# design.net
KiCad netlist of a schematic drawn in Altium Designer
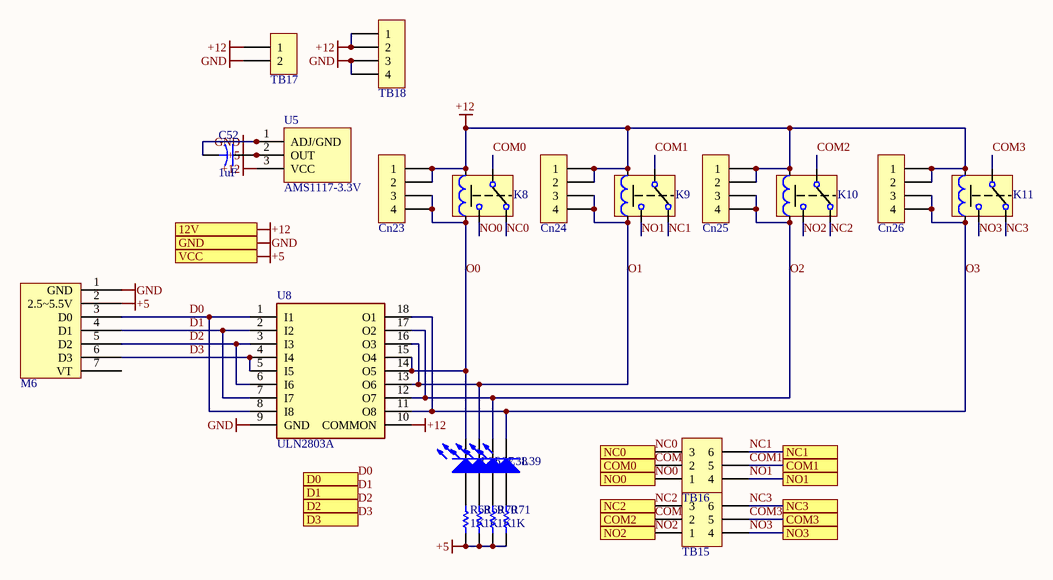
[diagram p0: 遙控繼電器.SchDoc]

(export (version "E")
  (design (tool "Eeschema 10.0.6"))
  (components
    (comp (ref "C52")
      (value "1uF")
      (footprint "CAP-1210")
      (description "電容")
      (libsource (lib "MyLibray") (part "Cap"))
    )
    (comp (ref "Cn23")
      (value "KF2510-4")
      (footprint "Connector_KF2510-4A")
      (description "接線端子")
      (libsource (lib "MyLibray") (part "Contact(4P)"))
    )
    (comp (ref "Cn24")
      (value "KF2510-4")
      (footprint "Connector_KF2510-4A")
      (description "接線端子")
      (libsource (lib "MyLibray") (part "Contact(4P)"))
    )
    (comp (ref "Cn25")
      (value "KF2510-4")
      (footprint "Connector_KF2510-4A")
      (description "接線端子")
      (libsource (lib "MyLibray") (part "Contact(4P)"))
    )
    (comp (ref "Cn26")
      (value "KF2510-4")
      (footprint "Connector_KF2510-4A")
      (description "接線端子")
      (libsource (lib "MyLibray") (part "Contact(4P)"))
    )
    (comp (ref "K8")
      (value "G2R-1-24VDC")
      (footprint "RELAY-HF41F-012-ZST")
      (description "繼電器")
      (libsource (lib "MyLibray") (part "Relay"))
    )
    (comp (ref "K9")
      (value "G2R-1-24VDC")
      (footprint "RELAY-HF41F-012-ZST")
      (description "繼電器")
      (libsource (lib "MyLibray") (part "Relay"))
    )
    (comp (ref "K10")
      (value "G2R-1-24VDC")
      (footprint "RELAY-HF41F-012-ZST")
      (description "繼電器")
      (libsource (lib "MyLibray") (part "Relay"))
    )
    (comp (ref "K11")
      (value "G2R-1-24VDC")
      (footprint "RELAY-HF41F-012-ZST")
      (description "繼電器")
      (libsource (lib "MyLibray") (part "Relay"))
    )
    (comp (ref "L36")
      (value "藍")
      (footprint "LED-1206")
      (description "LED")
      (libsource (lib "MyLibray") (part "LED"))
    )
    (comp (ref "L37")
      (value "藍")
      (footprint "LED-1206")
      (description "LED")
      (libsource (lib "MyLibray") (part "LED"))
    )
    (comp (ref "L38")
      (value "藍")
      (footprint "LED-1206")
      (description "LED")
      (libsource (lib "MyLibray") (part "LED"))
    )
    (comp (ref "L39")
      (value "藍")
      (footprint "LED-1206")
      (description "LED")
      (libsource (lib "MyLibray") (part "LED"))
    )
    (comp (ref "M6")
      (value "XR390")
      (footprint "XR390 Module")
      (description "遙控器模組")
      (libsource (lib "MyModule") (part "XR390"))
    )
    (comp (ref "R68")
      (value "1K")
      (footprint "Res-1206")
      (description "電阻")
      (libsource (lib "MyLibray") (part "Res"))
    )
    (comp (ref "R69")
      (value "1K")
      (footprint "Res-1206")
      (description "電阻")
      (libsource (lib "MyLibray") (part "Res"))
    )
    (comp (ref "R70")
      (value "1K")
      (footprint "Res-1206")
      (description "電阻")
      (libsource (lib "MyLibray") (part "Res"))
    )
    (comp (ref "R71")
      (value "1K")
      (footprint "Res-1206")
      (description "電阻")
      (libsource (lib "MyLibray") (part "Res"))
    )
    (comp (ref "TB15")
      (value "KF2EDGRT-5.08_6P")
      (footprint "Terminal block(KF2EDGRT-3.81_2*3P)")
      (description "端子台")
      (libsource (lib "MyLibray") (part "Terminal block(6P)"))
    )
    (comp (ref "TB16")
      (value "KF2EDGRT-5.08_6P")
      (footprint "Terminal block(KF2EDGRT-3.81_2*3P)")
      (description "端子台")
      (libsource (lib "MyLibray") (part "Terminal block(6P)"))
    )
    (comp (ref "TB17")
      (value "ZB25(2P)")
      (footprint "Terminal block(KF2EDGR-5.08 _2P)")
      (description "端子台")
      (libsource (lib "MyLibray") (part "Terminal block(2P)"))
    )
    (comp (ref "TB18")
      (value "KF2EDGRT-5.08_4P")
      (footprint "Terminal block(KF2EDGR-5.08 _4P)")
      (description "端子台")
      (libsource (lib "MyLibray") (part "Terminal block(4P)"))
    )
    (comp (ref "U5")
      (value "AMS1117-3.3V")
      (footprint "SOT 223")
      (description "降壓IC,LOD")
      (libsource (lib "MyLibray") (part "AMS1117"))
    )
    (comp (ref "U8")
      (value "ULN2803A")
      (footprint "DIP-18")
      (description "閘極驅動器 P型 50V 0.5A")
      (fields
        (field (name "MOUSER PART NUMBER") "757-TBD60183AFNGEL")
        (field (name "MANUFACTURER_PART_NUMBER") "TBD62083AFNG,EL")
      )
      (libsource (lib "MyLibray") (part "TBD62083A"))
    )
  )
  (nets
    (net (code "1") (name "+5") (class "Default")
      (node (ref "C52") (pin "1") (pinfunction "1_1") (pintype "passive"))
      (node (ref "M6") (pin "2") (pinfunction "2.5~5.5V_2") (pintype "passive"))
      (node (ref "R68") (pin "2") (pinfunction "2_2") (pintype "passive"))
      (node (ref "R69") (pin "2") (pinfunction "2_2") (pintype "passive"))
      (node (ref "R70") (pin "2") (pinfunction "2_2") (pintype "passive"))
      (node (ref "R71") (pin "2") (pinfunction "2_2") (pintype "passive"))
      (node (ref "U5") (pin "2") (pinfunction "OUT_2") (pintype "passive"))
    )
    (net (code "2") (name "+12") (class "Default")
      (node (ref "Cn23") (pin "1") (pinfunction "1_1") (pintype "passive"))
      (node (ref "Cn23") (pin "2") (pinfunction "2_2") (pintype "passive"))
      (node (ref "Cn24") (pin "1") (pinfunction "1_1") (pintype "passive"))
      (node (ref "Cn24") (pin "2") (pinfunction "2_2") (pintype "passive"))
      (node (ref "Cn25") (pin "1") (pinfunction "1_1") (pintype "passive"))
      (node (ref "Cn25") (pin "2") (pinfunction "2_2") (pintype "passive"))
      (node (ref "Cn26") (pin "1") (pinfunction "1_1") (pintype "passive"))
      (node (ref "Cn26") (pin "2") (pinfunction "2_2") (pintype "passive"))
      (node (ref "K10") (pin "4") (pinfunction "A1_4") (pintype "passive"))
      (node (ref "K11") (pin "4") (pinfunction "A1_4") (pintype "passive"))
      (node (ref "K8") (pin "4") (pinfunction "A1_4") (pintype "passive"))
      (node (ref "K9") (pin "4") (pinfunction "A1_4") (pintype "passive"))
      (node (ref "TB17") (pin "1") (pinfunction "1_1") (pintype "passive"))
      (node (ref "TB18") (pin "1") (pinfunction "1_1") (pintype "passive"))
      (node (ref "TB18") (pin "2") (pinfunction "2_2") (pintype "passive"))
      (node (ref "U5") (pin "3") (pinfunction "VCC_3") (pintype "power_in"))
      (node (ref "U8") (pin "10") (pinfunction "COMMON_10") (pintype "passive"))
    )
    (net (code "3") (name "/COM0") (class "Default")
      (node (ref "K8") (pin "1") (pinfunction "COM_1") (pintype "passive"))
      (node (ref "TB16") (pin "2") (pinfunction "2_2") (pintype "passive"))
    )
    (net (code "4") (name "/COM1") (class "Default")
      (node (ref "K9") (pin "1") (pinfunction "COM_1") (pintype "passive"))
      (node (ref "TB16") (pin "5") (pinfunction "5_5") (pintype "passive"))
    )
    (net (code "5") (name "/COM2") (class "Default")
      (node (ref "K10") (pin "1") (pinfunction "COM_1") (pintype "passive"))
      (node (ref "TB15") (pin "2") (pinfunction "2_2") (pintype "passive"))
    )
    (net (code "6") (name "/COM3") (class "Default")
      (node (ref "K11") (pin "1") (pinfunction "COM_1") (pintype "passive"))
      (node (ref "TB15") (pin "5") (pinfunction "5_5") (pintype "passive"))
    )
    (net (code "7") (name "/D0") (class "Default")
      (node (ref "M6") (pin "3") (pinfunction "D0_3") (pintype "passive"))
      (node (ref "U8") (pin "1") (pinfunction "I1_1") (pintype "passive"))
      (node (ref "U8") (pin "8") (pinfunction "I8_8") (pintype "passive"))
    )
    (net (code "8") (name "/D1") (class "Default")
      (node (ref "M6") (pin "4") (pinfunction "D1_4") (pintype "passive"))
      (node (ref "U8") (pin "2") (pinfunction "I2_2") (pintype "passive"))
      (node (ref "U8") (pin "7") (pinfunction "I7_7") (pintype "passive"))
    )
    (net (code "9") (name "/D2") (class "Default")
      (node (ref "M6") (pin "5") (pinfunction "D2_5") (pintype "passive"))
      (node (ref "U8") (pin "3") (pinfunction "I3_3") (pintype "passive"))
      (node (ref "U8") (pin "6") (pinfunction "I6_6") (pintype "passive"))
    )
    (net (code "10") (name "/D3") (class "Default")
      (node (ref "M6") (pin "6") (pinfunction "D3_6") (pintype "passive"))
      (node (ref "U8") (pin "4") (pinfunction "I4_4") (pintype "passive"))
      (node (ref "U8") (pin "5") (pinfunction "I5_5") (pintype "passive"))
    )
    (net (code "11") (name "/NC0") (class "Default")
      (node (ref "K8") (pin "3") (pinfunction "NC_3") (pintype "passive"))
      (node (ref "TB16") (pin "3") (pinfunction "3_3") (pintype "passive"))
    )
    (net (code "12") (name "/NC1") (class "Default")
      (node (ref "K9") (pin "3") (pinfunction "NC_3") (pintype "passive"))
      (node (ref "TB16") (pin "6") (pinfunction "6_6") (pintype "passive"))
    )
    (net (code "13") (name "/NC2") (class "Default")
      (node (ref "K10") (pin "3") (pinfunction "NC_3") (pintype "passive"))
      (node (ref "TB15") (pin "3") (pinfunction "3_3") (pintype "passive"))
    )
    (net (code "14") (name "/NC3") (class "Default")
      (node (ref "K11") (pin "3") (pinfunction "NC_3") (pintype "passive"))
      (node (ref "TB15") (pin "6") (pinfunction "6_6") (pintype "passive"))
    )
    (net (code "15") (name "/NO0") (class "Default")
      (node (ref "K8") (pin "2") (pinfunction "NO_2") (pintype "passive"))
      (node (ref "TB16") (pin "1") (pinfunction "1_1") (pintype "passive"))
    )
    (net (code "16") (name "/NO1") (class "Default")
      (node (ref "K9") (pin "2") (pinfunction "NO_2") (pintype "passive"))
      (node (ref "TB16") (pin "4") (pinfunction "4_4") (pintype "passive"))
    )
    (net (code "17") (name "/NO2") (class "Default")
      (node (ref "K10") (pin "2") (pinfunction "NO_2") (pintype "passive"))
      (node (ref "TB15") (pin "1") (pinfunction "1_1") (pintype "passive"))
    )
    (net (code "18") (name "/NO3") (class "Default")
      (node (ref "K11") (pin "2") (pinfunction "NO_2") (pintype "passive"))
      (node (ref "TB15") (pin "4") (pinfunction "4_4") (pintype "passive"))
    )
    (net (code "19") (name "/O0") (class "Default")
      (node (ref "Cn23") (pin "3") (pinfunction "3_3") (pintype "passive"))
      (node (ref "Cn23") (pin "4") (pinfunction "4_4") (pintype "passive"))
      (node (ref "K8") (pin "5") (pinfunction "A2_5") (pintype "passive"))
      (node (ref "L36") (pin "1") (pinfunction "K_1") (pintype "passive"))
      (node (ref "U8") (pin "14") (pinfunction "O5_14") (pintype "passive"))
      (node (ref "U8") (pin "15") (pinfunction "O4_15") (pintype "passive"))
    )
    (net (code "20") (name "/O1") (class "Default")
      (node (ref "Cn24") (pin "3") (pinfunction "3_3") (pintype "passive"))
      (node (ref "Cn24") (pin "4") (pinfunction "4_4") (pintype "passive"))
      (node (ref "K9") (pin "5") (pinfunction "A2_5") (pintype "passive"))
      (node (ref "L37") (pin "1") (pinfunction "K_1") (pintype "passive"))
      (node (ref "U8") (pin "13") (pinfunction "O6_13") (pintype "passive"))
      (node (ref "U8") (pin "16") (pinfunction "O3_16") (pintype "passive"))
    )
    (net (code "21") (name "/O2") (class "Default")
      (node (ref "Cn25") (pin "3") (pinfunction "3_3") (pintype "passive"))
      (node (ref "Cn25") (pin "4") (pinfunction "4_4") (pintype "passive"))
      (node (ref "K10") (pin "5") (pinfunction "A2_5") (pintype "passive"))
      (node (ref "L38") (pin "1") (pinfunction "K_1") (pintype "passive"))
      (node (ref "U8") (pin "12") (pinfunction "O7_12") (pintype "passive"))
      (node (ref "U8") (pin "17") (pinfunction "O2_17") (pintype "passive"))
    )
    (net (code "22") (name "/O3") (class "Default")
      (node (ref "Cn26") (pin "3") (pinfunction "3_3") (pintype "passive"))
      (node (ref "Cn26") (pin "4") (pinfunction "4_4") (pintype "passive"))
      (node (ref "K11") (pin "5") (pinfunction "A2_5") (pintype "passive"))
      (node (ref "L39") (pin "1") (pinfunction "K_1") (pintype "passive"))
      (node (ref "U8") (pin "11") (pinfunction "O8_11") (pintype "passive"))
      (node (ref "U8") (pin "18") (pinfunction "O1_18") (pintype "passive"))
    )
    (net (code "23") (name "GND") (class "Default")
      (node (ref "C52") (pin "2") (pinfunction "2_2") (pintype "passive"))
      (node (ref "M6") (pin "1") (pinfunction "GND_1") (pintype "passive"))
      (node (ref "TB17") (pin "2") (pinfunction "2_2") (pintype "passive"))
      (node (ref "TB18") (pin "3") (pinfunction "3_3") (pintype "passive"))
      (node (ref "TB18") (pin "4") (pinfunction "4_4") (pintype "passive"))
      (node (ref "U5") (pin "1") (pinfunction "ADJ/GND_1") (pintype "passive"))
      (node (ref "U8") (pin "9") (pinfunction "GND_9") (pintype "passive"))
    )
    (net (code "24") (name "Net-(L36-A)") (class "Default")
      (node (ref "L36") (pin "2") (pinfunction "A_2") (pintype "passive"))
      (node (ref "R68") (pin "1") (pinfunction "1_1") (pintype "passive"))
    )
    (net (code "25") (name "Net-(L37-A)") (class "Default")
      (node (ref "L37") (pin "2") (pinfunction "A_2") (pintype "passive"))
      (node (ref "R69") (pin "1") (pinfunction "1_1") (pintype "passive"))
    )
    (net (code "26") (name "Net-(L38-A)") (class "Default")
      (node (ref "L38") (pin "2") (pinfunction "A_2") (pintype "passive"))
      (node (ref "R70") (pin "1") (pinfunction "1_1") (pintype "passive"))
    )
    (net (code "27") (name "Net-(L39-A)") (class "Default")
      (node (ref "L39") (pin "2") (pinfunction "A_2") (pintype "passive"))
      (node (ref "R71") (pin "1") (pinfunction "1_1") (pintype "passive"))
    )
    (net (code "28") (name "unconnected-(M6-VT-Pad7)") (class "Default")
      (node (ref "M6") (pin "7") (pinfunction "VT_7") (pintype "passive"))
    )
  )
)
